# Sheet1.net
KiCad netlist of a schematic drawn in Altium Designer
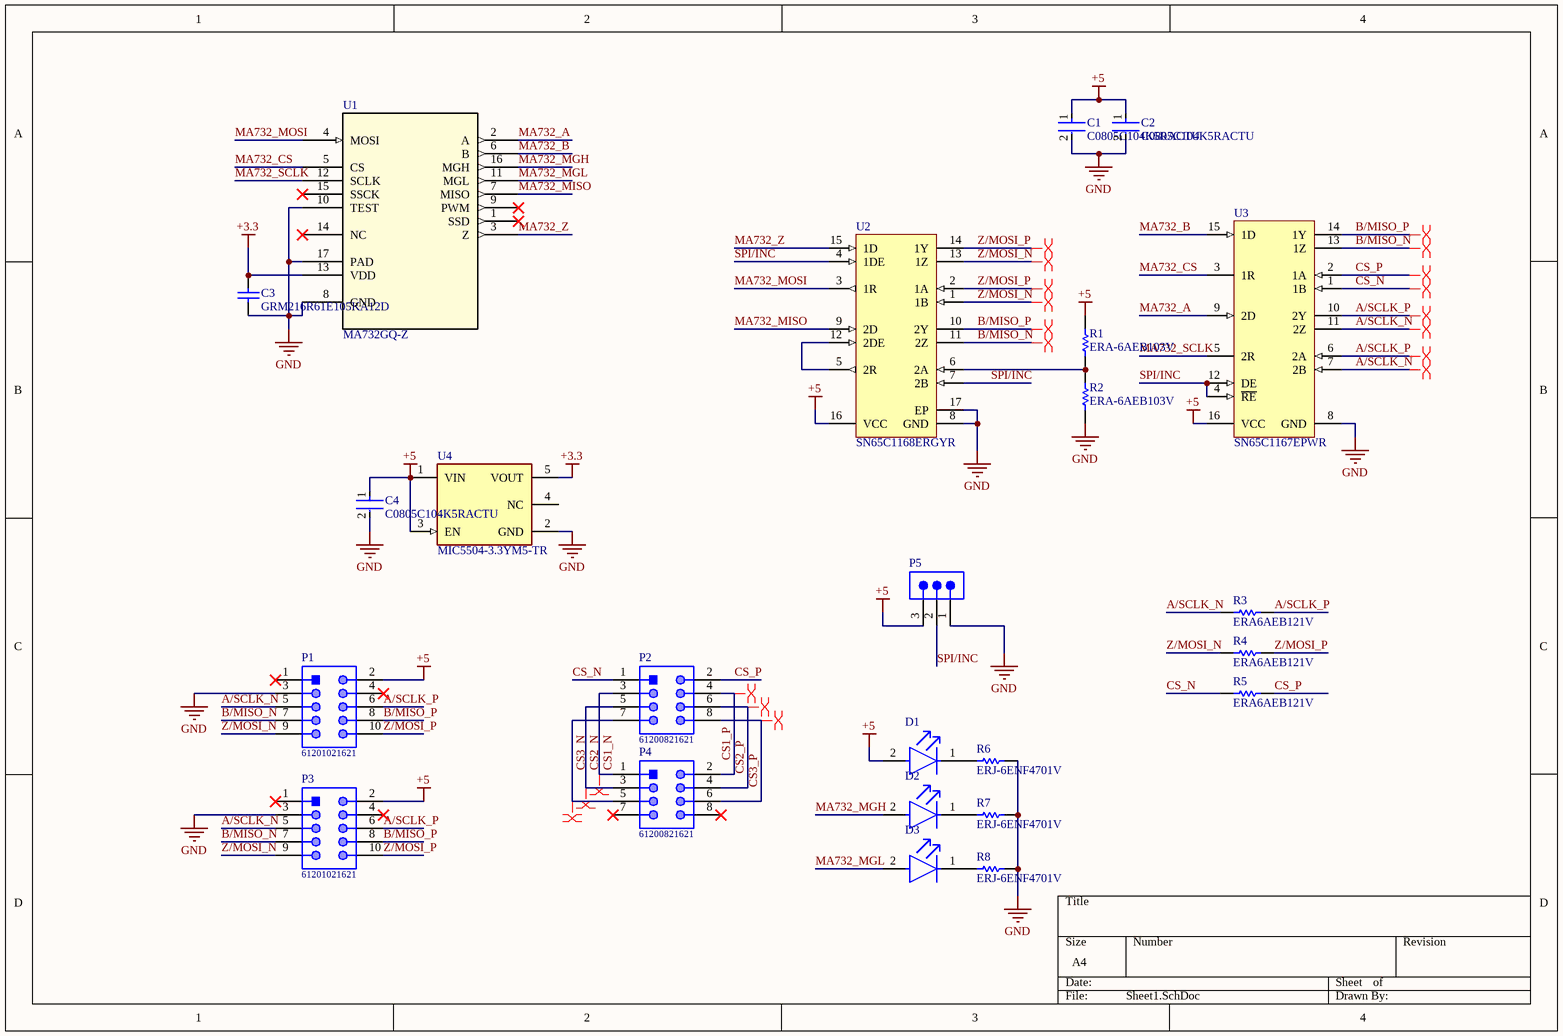
[diagram p0: Sheet1.SchDoc]

(export (version "E")
  (design (tool "Eeschema 10.0.6"))
  (components
    (comp (ref "C1")
      (value "C0805C104K5RACTU")
      (footprint "FP-C0805C-DN-MFG")
      (description "CAP CER 0.1UF 50V X7R 0805")
      (fields
        (field (name "MANUFACTURER") "KEMET")
        (field (name "OCTOPART") "https://octopart.com/c0805c104k5ractu-kemet-143926")
      )
      (libsource (lib "Altium Content Vault") (part "b4654b650e69147ec39a6b967a45e02"))
    )
    (comp (ref "C2")
      (value "C0805C104K5RACTU")
      (footprint "FP-C0805C-DN-MFG")
      (description "CAP CER 0.1UF 50V X7R 0805")
      (fields
        (field (name "MANUFACTURER") "KEMET")
        (field (name "OCTOPART") "https://octopart.com/c0805c104k5ractu-kemet-143926")
      )
      (libsource (lib "Altium Content Vault") (part "b4654b650e69147ec39a6b967a45e02"))
    )
    (comp (ref "C3")
      (value "GRM216R61E105KA12D")
      (footprint "CAPC2013X70X45NL10T25")
      (fields (field (name "MANUFACTURER") "Murata"))
      (libsource (lib "Altium Content Vault") (part "CAP"))
    )
    (comp (ref "C4")
      (value "C0805C104K5RACTU")
      (footprint "FP-C0805C-DN-MFG")
      (description "CAP CER 0.1UF 50V X7R 0805")
      (fields
        (field (name "MANUFACTURER") "KEMET")
        (field (name "OCTOPART") "https://octopart.com/c0805c104k5ractu-kemet-143926")
      )
      (libsource (lib "Altium Content Vault") (part "b4654b650e69147ec39a6b967a45e02"))
    )
    (comp (ref "D1")
      (value "150080SS75000")
      (footprint "FP-150080SS75000-MFG")
      (description "LED RED CLEAR 0805 SMD")
      (libsource (lib "Altium Content Vault") (part "8706943c75ba83719d021d2fdc84c58"))
    )
    (comp (ref "D2")
      (value "150080SS75000")
      (footprint "FP-150080SS75000-MFG")
      (description "LED RED CLEAR 0805 SMD")
      (libsource (lib "Altium Content Vault") (part "8706943c75ba83719d021d2fdc84c58"))
    )
    (comp (ref "D3")
      (value "150080SS75000")
      (footprint "FP-150080SS75000-MFG")
      (description "LED RED CLEAR 0805 SMD")
      (libsource (lib "Altium Content Vault") (part "8706943c75ba83719d021d2fdc84c58"))
    )
    (comp (ref "P1")
      (value "61201021621")
      (footprint "61201021621")
      (description "Male Box Header WR-BHD, THT, Vertical, pitch 2.54 mm, 10 pins")
      (fields (field (name "MANUFACTURER") "Wurth Elektronik") (field (name "PUBLISHER") "WurthElektronik"))
      (libsource (lib "Altium Content Vault") (part "WE-CN-2P-M-R10"))
    )
    (comp (ref "P2")
      (value "61200821621")
      (footprint "61200821621")
      (description "Male Box Header WR-BHD, THT, Vertical, pitch 2.54 mm, 8 pins")
      (fields (field (name "MANUFACTURER") "Wurth Elektronik") (field (name "PUBLISHER") "WurthElektronik"))
      (libsource (lib "Altium Content Vault") (part "WE-CN-2P-M-R8"))
    )
    (comp (ref "P3")
      (value "61201021621")
      (footprint "61201021621")
      (description "Male Box Header WR-BHD, THT, Vertical, pitch 2.54 mm, 10 pins")
      (fields (field (name "MANUFACTURER") "Wurth Elektronik") (field (name "PUBLISHER") "WurthElektronik"))
      (libsource (lib "Altium Content Vault") (part "WE-CN-2P-M-R10"))
    )
    (comp (ref "P4")
      (value "61200821621")
      (footprint "61200821621")
      (description "Male Box Header WR-BHD, THT, Vertical, pitch 2.54 mm, 8 pins")
      (fields (field (name "MANUFACTURER") "Wurth Elektronik") (field (name "PUBLISHER") "WurthElektronik"))
      (libsource (lib "Altium Content Vault") (part "WE-CN-2P-M-R8"))
    )
    (comp (ref "P5")
      (value "TSW-103-07-T-S")
      (footprint "SMTC-TSW-103-07-X-S")
      (description "0.025\" SQ Post Header, Through-hole, Vertical, -55 to 105 degC, 2.54 mm Pitch, 3-Pin, Male, RoHS")
      (fields (field (name "MANUFACTURER") "Samtec"))
      (libsource (lib "Altium Content Vault") (part "SMTC-TSW-103-X-X-S-X"))
    )
    (comp (ref "R1")
      (value "ERA-6AEB103V")
      (footprint "RESC2013X60X40LL20T25_A")
      (fields (field (name "TOLERANCE") "0.1%") (field (name "MANUFACTURER") "Panasonic"))
      (libsource (lib "Altium Content Vault") (part "RES-2"))
    )
    (comp (ref "R2")
      (value "ERA-6AEB103V")
      (footprint "RESC2013X60X40LL20T25_A")
      (fields (field (name "TOLERANCE") "0.1%") (field (name "MANUFACTURER") "Panasonic"))
      (libsource (lib "Altium Content Vault") (part "RES-2"))
    )
    (comp (ref "R3")
      (value "ERA6AEB121V")
      (footprint "RESC2013X60X40ML20T25")
      (fields (field (name "MANUFACTURER") "Panasonic"))
      (libsource (lib "Altium Content Vault") (part "RES"))
    )
    (comp (ref "R4")
      (value "ERA6AEB121V")
      (footprint "RESC2013X60X40ML20T25")
      (fields (field (name "MANUFACTURER") "Panasonic"))
      (libsource (lib "Altium Content Vault") (part "RES"))
    )
    (comp (ref "R5")
      (value "ERA6AEB121V")
      (footprint "RESC2013X60X40ML20T25")
      (fields (field (name "MANUFACTURER") "Panasonic"))
      (libsource (lib "Altium Content Vault") (part "RES"))
    )
    (comp (ref "R6")
      (value "ERJ-6ENF4701V")
      (footprint "RESC2013X70X40NL20T20")
      (description "Chip Resistor, 4.7 KOhm, +/- 1%, 0.125 W, -55 to 155 degC, 0805 (2012 Metric), RoHS, Tape and Reel")
      (fields (field (name "MANUFACTURER") "Panasonic"))
      (libsource (lib "Altium Content Vault") (part "RES-2"))
    )
    (comp (ref "R7")
      (value "ERJ-6ENF4701V")
      (footprint "RESC2013X70X40NL20T20")
      (description "Chip Resistor, 4.7 KOhm, +/- 1%, 0.125 W, -55 to 155 degC, 0805 (2012 Metric), RoHS, Tape and Reel")
      (fields (field (name "MANUFACTURER") "Panasonic"))
      (libsource (lib "Altium Content Vault") (part "RES-2"))
    )
    (comp (ref "R8")
      (value "ERJ-6ENF4701V")
      (footprint "RESC2013X70X40NL20T20")
      (description "Chip Resistor, 4.7 KOhm, +/- 1%, 0.125 W, -55 to 155 degC, 0805 (2012 Metric), RoHS, Tape and Reel")
      (fields (field (name "MANUFACTURER") "Panasonic"))
      (libsource (lib "Altium Content Vault") (part "RES-2"))
    )
    (comp (ref "U1")
      (value "MA732GQ-Z")
      (footprint "QFN-16_MA732")
      (description "No Description Available")
      (fields (field (name "COPYRIGHT") "Copyright (C) 2023 Ultra Librarian. All rights reserved."))
      (libsource (lib "MA732GQ-Z") (part "MA732GQ-Z"))
    )
    (comp (ref "U2")
      (value "SN65C1168ERGYR")
      (footprint "RGY0016A_V")
      (description "None")
      (libsource (lib "Altium Content Vault") (part "TI-SN65C1168E-VQFN_RGY-16"))
    )
    (comp (ref "U3")
      (value "SN65C1167EPWR")
      (footprint "PW0016A_M")
      (fields (field (name "MANUFACTURER") "Texas Instruments"))
      (libsource (lib "Altium Content Vault") (part "TI-SN65C1167E-TSSOP_PW-16"))
    )
    (comp (ref "U4")
      (value "MIC5504-3.3YM5-TR")
      (footprint "FP-SOT23-5LD-PL-1-MFG")
      (description "IC REG LINEAR 3.3V 300MA SOT23-5")
      (libsource (lib "Altium Content Vault") (part "96048095611b4a9579e1e315950d302"))
    )
  )
  (nets
    (net (code "1") (name "+3.3") (class "Default")
      (node (ref "C3") (pin "2") (pinfunction "2_2") (pintype "passive"))
      (node (ref "U1") (pin "13") (pinfunction "VDD_13") (pintype "power_in"))
      (node (ref "U4") (pin "5") (pinfunction "VOUT_5") (pintype "power_in"))
    )
    (net (code "2") (name "+5") (class "Default")
      (node (ref "C1") (pin "1") (pinfunction "1_1") (pintype "passive"))
      (node (ref "C2") (pin "1") (pinfunction "1_1") (pintype "passive"))
      (node (ref "C4") (pin "1") (pinfunction "1_1") (pintype "passive"))
      (node (ref "D1") (pin "2") (pinfunction "A_2") (pintype "passive"))
      (node (ref "P1") (pin "2") (pinfunction "2_2") (pintype "passive"))
      (node (ref "P3") (pin "2") (pinfunction "2_2") (pintype "passive"))
      (node (ref "P5") (pin "3") (pinfunction "3_3") (pintype "passive"))
      (node (ref "R1") (pin "2") (pinfunction "2_2") (pintype "passive"))
      (node (ref "U2") (pin "16") (pinfunction "VCC_16") (pintype "power_in"))
      (node (ref "U3") (pin "16") (pinfunction "VCC_16") (pintype "power_in"))
      (node (ref "U4") (pin "1") (pinfunction "VIN_1") (pintype "power_in"))
      (node (ref "U4") (pin "3") (pinfunction "EN_3") (pintype "input"))
    )
    (net (code "3") (name "/A{slash}SCLK_N") (class "Default")
      (node (ref "P1") (pin "5") (pinfunction "5_5") (pintype "passive"))
      (node (ref "P3") (pin "5") (pinfunction "5_5") (pintype "passive"))
      (node (ref "R3") (pin "1") (pinfunction "1_1") (pintype "passive"))
      (node (ref "U3") (pin "11") (pinfunction "2Z_11") (pintype "tri_state"))
      (node (ref "U3") (pin "7") (pinfunction "2B_7") (pintype "input"))
    )
    (net (code "4") (name "/A{slash}SCLK_P") (class "Default")
      (node (ref "P1") (pin "6") (pinfunction "6_6") (pintype "passive"))
      (node (ref "P3") (pin "6") (pinfunction "6_6") (pintype "passive"))
      (node (ref "R3") (pin "2") (pinfunction "2_2") (pintype "passive"))
      (node (ref "U3") (pin "10") (pinfunction "2Y_10") (pintype "tri_state"))
      (node (ref "U3") (pin "6") (pinfunction "2A_6") (pintype "input"))
    )
    (net (code "5") (name "/B{slash}MISO_N") (class "Default")
      (node (ref "P1") (pin "7") (pinfunction "7_7") (pintype "passive"))
      (node (ref "P3") (pin "7") (pinfunction "7_7") (pintype "passive"))
      (node (ref "U2") (pin "11") (pinfunction "2Z_11") (pintype "tri_state"))
      (node (ref "U3") (pin "13") (pinfunction "1Z_13") (pintype "tri_state"))
    )
    (net (code "6") (name "/B{slash}MISO_P") (class "Default")
      (node (ref "P1") (pin "8") (pinfunction "8_8") (pintype "passive"))
      (node (ref "P3") (pin "8") (pinfunction "8_8") (pintype "passive"))
      (node (ref "U2") (pin "10") (pinfunction "2Y_10") (pintype "tri_state"))
      (node (ref "U3") (pin "14") (pinfunction "1Y_14") (pintype "tri_state"))
    )
    (net (code "7") (name "/CS1_N") (class "Default")
      (node (ref "P2") (pin "3") (pinfunction "3_3") (pintype "passive"))
      (node (ref "P4") (pin "1") (pinfunction "1_1") (pintype "passive"))
    )
    (net (code "8") (name "/CS1_P") (class "Default")
      (node (ref "P2") (pin "4") (pinfunction "4_4") (pintype "passive"))
      (node (ref "P4") (pin "2") (pinfunction "2_2") (pintype "passive"))
    )
    (net (code "9") (name "/CS2_N") (class "Default")
      (node (ref "P2") (pin "5") (pinfunction "5_5") (pintype "passive"))
      (node (ref "P4") (pin "3") (pinfunction "3_3") (pintype "passive"))
    )
    (net (code "10") (name "/CS2_P") (class "Default")
      (node (ref "P2") (pin "6") (pinfunction "6_6") (pintype "passive"))
      (node (ref "P4") (pin "4") (pinfunction "4_4") (pintype "passive"))
    )
    (net (code "11") (name "/CS3_N") (class "Default")
      (node (ref "P2") (pin "7") (pinfunction "7_7") (pintype "passive"))
      (node (ref "P4") (pin "5") (pinfunction "5_5") (pintype "passive"))
    )
    (net (code "12") (name "/CS3_P") (class "Default")
      (node (ref "P2") (pin "8") (pinfunction "8_8") (pintype "passive"))
      (node (ref "P4") (pin "6") (pinfunction "6_6") (pintype "passive"))
    )
    (net (code "13") (name "/CS_N") (class "Default")
      (node (ref "P2") (pin "1") (pinfunction "1_1") (pintype "passive"))
      (node (ref "R5") (pin "1") (pinfunction "1_1") (pintype "passive"))
      (node (ref "U3") (pin "1") (pinfunction "1B_1") (pintype "input"))
    )
    (net (code "14") (name "/CS_P") (class "Default")
      (node (ref "P2") (pin "2") (pinfunction "2_2") (pintype "passive"))
      (node (ref "R5") (pin "2") (pinfunction "2_2") (pintype "passive"))
      (node (ref "U3") (pin "2") (pinfunction "1A_2") (pintype "input"))
    )
    (net (code "15") (name "/MA732_A") (class "Default")
      (node (ref "U1") (pin "2") (pinfunction "A_2") (pintype "output"))
      (node (ref "U3") (pin "9") (pinfunction "2D_9") (pintype "input"))
    )
    (net (code "16") (name "/MA732_B") (class "Default")
      (node (ref "U1") (pin "6") (pinfunction "B_6") (pintype "output"))
      (node (ref "U3") (pin "15") (pinfunction "1D_15") (pintype "input"))
    )
    (net (code "17") (name "/MA732_CS") (class "Default")
      (node (ref "U1") (pin "5") (pinfunction "CS_5") (pintype "passive"))
      (node (ref "U3") (pin "3") (pinfunction "1R_3") (pintype "tri_state"))
    )
    (net (code "18") (name "/MA732_MGH") (class "Default")
      (node (ref "D2") (pin "2") (pinfunction "A_2") (pintype "passive"))
      (node (ref "U1") (pin "16") (pinfunction "MGH_16") (pintype "output"))
    )
    (net (code "19") (name "/MA732_MGL") (class "Default")
      (node (ref "D3") (pin "2") (pinfunction "A_2") (pintype "passive"))
      (node (ref "U1") (pin "11") (pinfunction "MGL_11") (pintype "output"))
    )
    (net (code "20") (name "/MA732_MISO") (class "Default")
      (node (ref "U1") (pin "7") (pinfunction "MISO_7") (pintype "output"))
      (node (ref "U2") (pin "9") (pinfunction "2D_9") (pintype "input"))
    )
    (net (code "21") (name "/MA732_MOSI") (class "Default")
      (node (ref "U1") (pin "4") (pinfunction "MOSI_4") (pintype "input"))
      (node (ref "U2") (pin "3") (pinfunction "1R_3") (pintype "output"))
    )
    (net (code "22") (name "/MA732_SCLK") (class "Default")
      (node (ref "U1") (pin "12") (pinfunction "SCLK_12") (pintype "passive"))
      (node (ref "U3") (pin "5") (pinfunction "2R_5") (pintype "tri_state"))
    )
    (net (code "23") (name "/MA732_Z") (class "Default")
      (node (ref "U1") (pin "3") (pinfunction "Z_3") (pintype "output"))
      (node (ref "U2") (pin "15") (pinfunction "1D_15") (pintype "input"))
    )
    (net (code "24") (name "/SPI{slash}INC") (class "Default")
      (node (ref "P5") (pin "2") (pinfunction "2_2") (pintype "passive"))
      (node (ref "U2") (pin "4") (pinfunction "1DE_4") (pintype "input"))
      (node (ref "U2") (pin "7") (pinfunction "2B_7") (pintype "input"))
      (node (ref "U3") (pin "12") (pinfunction "DE_12") (pintype "input"))
      (node (ref "U3") (pin "4") (pinfunction "~{RE}_4") (pintype "input"))
    )
    (net (code "25") (name "/Z{slash}MOSI_N") (class "Default")
      (node (ref "P1") (pin "9") (pinfunction "9_9") (pintype "passive"))
      (node (ref "P3") (pin "9") (pinfunction "9_9") (pintype "passive"))
      (node (ref "R4") (pin "1") (pinfunction "1_1") (pintype "passive"))
      (node (ref "U2") (pin "1") (pinfunction "1B_1") (pintype "input"))
      (node (ref "U2") (pin "13") (pinfunction "1Z_13") (pintype "tri_state"))
    )
    (net (code "26") (name "/Z{slash}MOSI_P") (class "Default")
      (node (ref "P1") (pin "10") (pinfunction "10_10") (pintype "passive"))
      (node (ref "P3") (pin "10") (pinfunction "10_10") (pintype "passive"))
      (node (ref "R4") (pin "2") (pinfunction "2_2") (pintype "passive"))
      (node (ref "U2") (pin "14") (pinfunction "1Y_14") (pintype "tri_state"))
      (node (ref "U2") (pin "2") (pinfunction "1A_2") (pintype "input"))
    )
    (net (code "27") (name "GND") (class "Default")
      (node (ref "C1") (pin "2") (pinfunction "2_2") (pintype "passive"))
      (node (ref "C2") (pin "2") (pinfunction "2_2") (pintype "passive"))
      (node (ref "C3") (pin "1") (pinfunction "1_1") (pintype "passive"))
      (node (ref "C4") (pin "2") (pinfunction "2_2") (pintype "passive"))
      (node (ref "P1") (pin "3") (pinfunction "3_3") (pintype "passive"))
      (node (ref "P3") (pin "3") (pinfunction "3_3") (pintype "passive"))
      (node (ref "P5") (pin "1") (pinfunction "1_1") (pintype "passive"))
      (node (ref "R2") (pin "1") (pinfunction "1_1") (pintype "passive"))
      (node (ref "R6") (pin "2") (pinfunction "2_2") (pintype "passive"))
      (node (ref "R7") (pin "2") (pinfunction "2_2") (pintype "passive"))
      (node (ref "R8") (pin "2") (pinfunction "2_2") (pintype "passive"))
      (node (ref "U1") (pin "10") (pinfunction "TEST_10") (pintype "passive"))
      (node (ref "U1") (pin "17") (pinfunction "PAD_17") (pintype "power_in"))
      (node (ref "U1") (pin "8") (pinfunction "GND_8") (pintype "power_in"))
      (node (ref "U2") (pin "17") (pinfunction "EP_17") (pintype "passive"))
      (node (ref "U2") (pin "8") (pinfunction "GND_8") (pintype "power_in"))
      (node (ref "U3") (pin "8") (pinfunction "GND_8") (pintype "power_in"))
      (node (ref "U4") (pin "2") (pinfunction "GND_2") (pintype "power_in"))
    )
    (net (code "28") (name "Net-(D1-C)") (class "Default")
      (node (ref "D1") (pin "1") (pinfunction "C_1") (pintype "passive"))
      (node (ref "R6") (pin "1") (pinfunction "1_1") (pintype "passive"))
    )
    (net (code "29") (name "Net-(D2-C)") (class "Default")
      (node (ref "D2") (pin "1") (pinfunction "C_1") (pintype "passive"))
      (node (ref "R7") (pin "1") (pinfunction "1_1") (pintype "passive"))
    )
    (net (code "30") (name "Net-(D3-C)") (class "Default")
      (node (ref "D3") (pin "1") (pinfunction "C_1") (pintype "passive"))
      (node (ref "R8") (pin "1") (pinfunction "1_1") (pintype "passive"))
    )
    (net (code "31") (name "Net-(U2-2A)") (class "Default")
      (node (ref "R1") (pin "1") (pinfunction "1_1") (pintype "passive"))
      (node (ref "R2") (pin "2") (pinfunction "2_2") (pintype "passive"))
      (node (ref "U2") (pin "6") (pinfunction "2A_6") (pintype "input"))
    )
    (net (code "32") (name "Net-(U2-2DE)") (class "Default")
      (node (ref "U2") (pin "12") (pinfunction "2DE_12") (pintype "input"))
      (node (ref "U2") (pin "5") (pinfunction "2R_5") (pintype "output"))
    )
    (net (code "33") (name "unconnected-(P1-Pad1)") (class "Default")
      (node (ref "P1") (pin "1") (pinfunction "1_1") (pintype "passive+no_connect"))
    )
    (net (code "34") (name "unconnected-(P1-Pad4)") (class "Default")
      (node (ref "P1") (pin "4") (pinfunction "4_4") (pintype "passive+no_connect"))
    )
    (net (code "35") (name "unconnected-(P3-Pad1)") (class "Default")
      (node (ref "P3") (pin "1") (pinfunction "1_1") (pintype "passive+no_connect"))
    )
    (net (code "36") (name "unconnected-(P3-Pad4)") (class "Default")
      (node (ref "P3") (pin "4") (pinfunction "4_4") (pintype "passive+no_connect"))
    )
    (net (code "37") (name "unconnected-(P4-Pad7)") (class "Default")
      (node (ref "P4") (pin "7") (pinfunction "7_7") (pintype "passive+no_connect"))
    )
    (net (code "38") (name "unconnected-(P4-Pad8)") (class "Default")
      (node (ref "P4") (pin "8") (pinfunction "8_8") (pintype "passive+no_connect"))
    )
    (net (code "39") (name "unconnected-(U1-NC-Pad14)") (class "Default")
      (node (ref "U1") (pin "14") (pinfunction "NC_14") (pintype "passive+no_connect"))
    )
    (net (code "40") (name "unconnected-(U1-PWM-Pad9)") (class "Default")
      (node (ref "U1") (pin "9") (pinfunction "PWM_9") (pintype "output+no_connect"))
    )
    (net (code "41") (name "unconnected-(U1-SSCK-Pad15)") (class "Default")
      (node (ref "U1") (pin "15") (pinfunction "SSCK_15") (pintype "passive+no_connect"))
    )
    (net (code "42") (name "unconnected-(U1-SSD-Pad1)") (class "Default")
      (node (ref "U1") (pin "1") (pinfunction "SSD_1") (pintype "output+no_connect"))
    )
    (net (code "43") (name "unconnected-(U4-NC-Pad4)") (class "Default")
      (node (ref "U4") (pin "4") (pinfunction "NC_4") (pintype "passive"))
    )
  )
)
